# arduino_shield.net
KiCad netlist of a schematic drawn in EAGLE
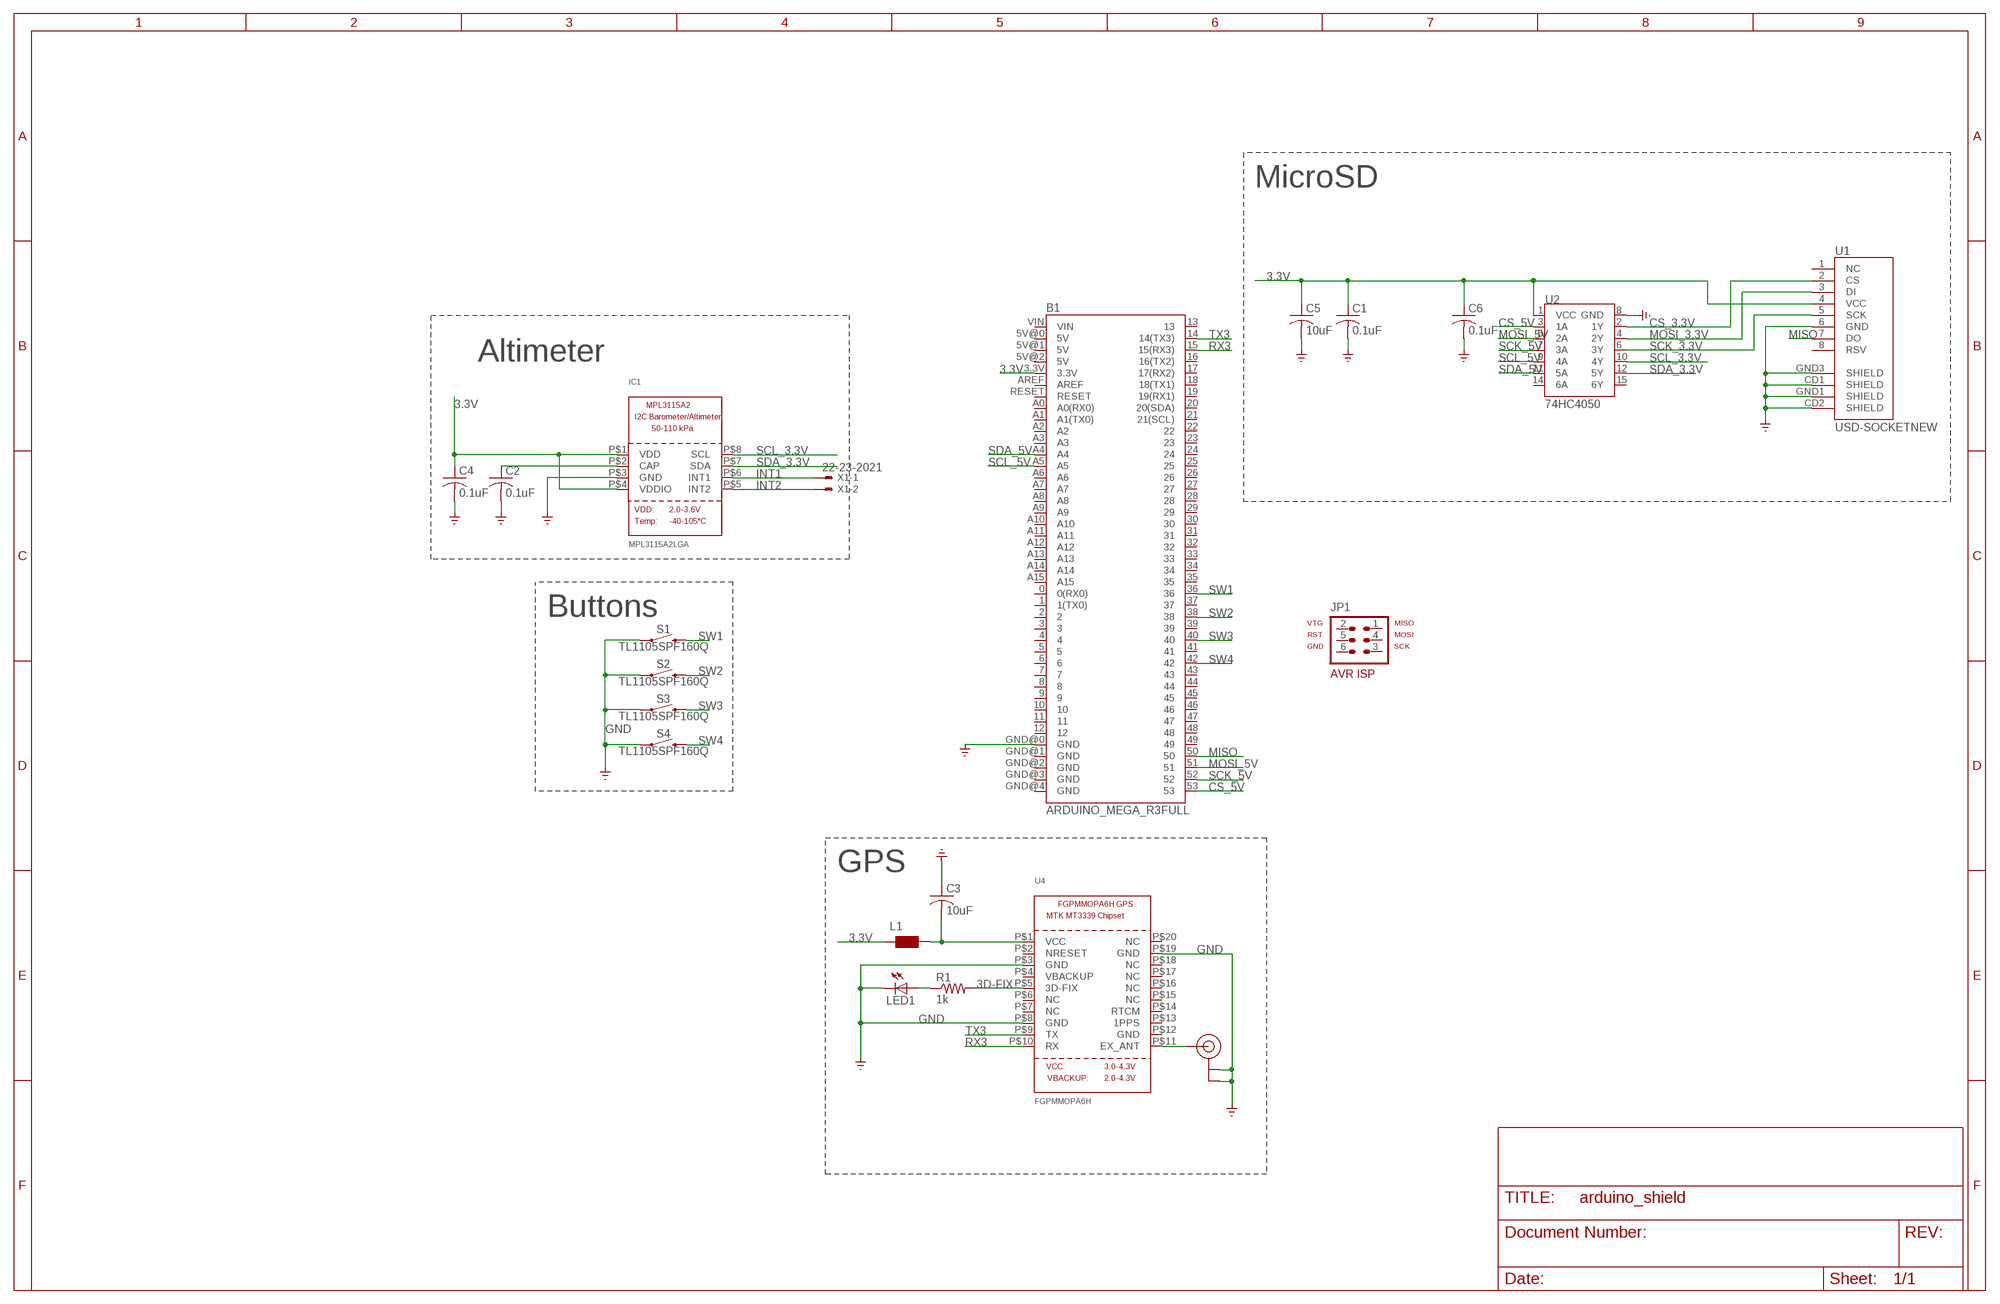
[diagram p0: schematic, sheet 1]

(export (version "E")
  (design (tool "Eeschema 10.0.6"))
  (components
    (comp (ref "B1")
      (value "ARDUINO_MEGA_R3FULL")
      (footprint "eagle-import:ARDUINO_MEGA")
      (libsource (lib "eagle-import") (part "ARDUINO_MEGA_R3FULL"))
    )
    (comp (ref "C1")
      (value "0.1uF")
      (footprint "eagle-import:C1206")
      (libsource (lib "eagle-import") (part "C-USC1206"))
    )
    (comp (ref "C2")
      (value "0.1uF")
      (footprint "eagle-import:C1206")
      (libsource (lib "eagle-import") (part "C-USC1206"))
    )
    (comp (ref "C3")
      (value "10uF")
      (footprint "eagle-import:C1206")
      (libsource (lib "eagle-import") (part "C-USC1206"))
    )
    (comp (ref "C4")
      (value "0.1uF")
      (footprint "eagle-import:C1206")
      (libsource (lib "eagle-import") (part "C-USC1206"))
    )
    (comp (ref "C5")
      (value "10uF")
      (footprint "eagle-import:C1206")
      (libsource (lib "eagle-import") (part "C-USC1206"))
    )
    (comp (ref "C6")
      (value "0.1uF")
      (footprint "eagle-import:C1206")
      (libsource (lib "eagle-import") (part "C-USC1206"))
    )
    (comp (ref "IC1")
      (value "MPL3115A2LGA")
      (footprint "eagle-import:LGA8")
      (libsource (lib "eagle-import") (part "MPL3115A2LGA"))
    )
    (comp (ref "JP1")
      (value "AVR-ISP-6")
      (footprint "eagle-import:AVR-ISP-6")
      (libsource (lib "eagle-import") (part "AVR-ISP-6"))
    )
    (comp (ref "L1")
      (value "WE-CBF_1206")
      (footprint "eagle-import:1206")
      (libsource (lib "eagle-import") (part "WE-CBF_1206"))
    )
    (comp (ref "LED1")
      (value "LEDSMT1206")
      (footprint "eagle-import:1206")
      (libsource (lib "eagle-import") (part "LEDSMT1206"))
    )
    (comp (ref "R1")
      (value "1k")
      (footprint "eagle-import:R1206")
      (libsource (lib "eagle-import") (part "R-US_R1206"))
    )
    (comp (ref "S1")
      (value "TL1105SPF160Q")
      (footprint "eagle-import:TACTILE_SWITCH_PTH_6.0MM")
      (libsource (lib "eagle-import") (part "MOMENTARY-SWITCH-SPST-PTH-6.0MM"))
    )
    (comp (ref "S2")
      (value "TL1105SPF160Q")
      (footprint "eagle-import:TACTILE_SWITCH_PTH_6.0MM")
      (libsource (lib "eagle-import") (part "MOMENTARY-SWITCH-SPST-PTH-6.0MM"))
    )
    (comp (ref "S3")
      (value "TL1105SPF160Q")
      (footprint "eagle-import:TACTILE_SWITCH_PTH_6.0MM")
      (libsource (lib "eagle-import") (part "MOMENTARY-SWITCH-SPST-PTH-6.0MM"))
    )
    (comp (ref "S4")
      (value "TL1105SPF160Q")
      (footprint "eagle-import:TACTILE_SWITCH_PTH_6.0MM")
      (libsource (lib "eagle-import") (part "MOMENTARY-SWITCH-SPST-PTH-6.0MM"))
    )
    (comp (ref "U$20")
      (value "U.FL")
      (footprint "eagle-import:U.FL")
      (libsource (lib "eagle-import") (part "U.FL"))
    )
    (comp (ref "U1")
      (value "USD-SOCKETNEW")
      (footprint "eagle-import:MICRO-SD-SOCKET-PP")
      (libsource (lib "eagle-import") (part "USD-SOCKETNEW"))
    )
    (comp (ref "U2")
      (value "74HC4050")
      (footprint "eagle-import:SO16")
      (libsource (lib "eagle-import") (part "HEX_CONVERTER"))
    )
    (comp (ref "U4")
      (value "FGPMMOPA6H")
      (footprint "eagle-import:FGPMMOPA6H")
      (libsource (lib "eagle-import") (part "GPS_FGPMMOPA6H"))
    )
    (comp (ref "X1")
      (value "22-23-2021")
      (footprint "eagle-import:22-23-2021")
      (fields (field (name "MF") "MOLEX"))
      (libsource (lib "eagle-import") (part "22-23-2021"))
    )
  )
  (nets
    (net (code "1") (name "/3.3V") (class "Default")
      (node (ref "B1") (pin "3.3V") (pinfunction "3.3V_3.3V") (pintype "bidirectional"))
      (node (ref "C1") (pin "1") (pinfunction "1_1") (pintype "passive"))
      (node (ref "C4") (pin "1") (pinfunction "1_1") (pintype "passive"))
      (node (ref "C5") (pin "1") (pinfunction "1_1") (pintype "passive"))
      (node (ref "C6") (pin "1") (pinfunction "1_1") (pintype "passive"))
      (node (ref "IC1") (pin "P$1") (pinfunction "VDD_P$1") (pintype "power_in"))
      (node (ref "IC1") (pin "P$4") (pinfunction "VDDIO_P$4") (pintype "power_in"))
      (node (ref "L1") (pin "1") (pinfunction "1_1") (pintype "passive"))
      (node (ref "U1") (pin "4") (pinfunction "VCC_4") (pintype "bidirectional"))
      (node (ref "U2") (pin "1") (pinfunction "VCC_1") (pintype "bidirectional"))
    )
    (net (code "2") (name "/3D-FIX") (class "Default")
      (node (ref "R1") (pin "2") (pinfunction "2_2") (pintype "passive"))
      (node (ref "U4") (pin "P$5") (pinfunction "3D-FIX_P$5") (pintype "bidirectional"))
    )
    (net (code "3") (name "/CS_3.3V") (class "Default")
      (node (ref "U1") (pin "2") (pinfunction "CS_2") (pintype "bidirectional"))
      (node (ref "U2") (pin "2") (pinfunction "1Y_2") (pintype "bidirectional"))
    )
    (net (code "4") (name "/CS_5V") (class "Default")
      (node (ref "B1") (pin "53") (pinfunction "53_53") (pintype "bidirectional"))
      (node (ref "U2") (pin "3") (pinfunction "1A_3") (pintype "bidirectional"))
    )
    (net (code "5") (name "/INT1") (class "Default")
      (node (ref "IC1") (pin "P$6") (pinfunction "INT1_P$6") (pintype "output"))
      (node (ref "X1") (pin "1") (pinfunction "S_1") (pintype "passive"))
    )
    (net (code "6") (name "/INT2") (class "Default")
      (node (ref "IC1") (pin "P$5") (pinfunction "INT2_P$5") (pintype "output"))
      (node (ref "X1") (pin "2") (pinfunction "S_2") (pintype "passive"))
    )
    (net (code "7") (name "/MISO") (class "Default")
      (node (ref "B1") (pin "50") (pinfunction "50_50") (pintype "bidirectional"))
      (node (ref "U1") (pin "7") (pinfunction "DO_7") (pintype "bidirectional"))
    )
    (net (code "8") (name "/MOSI_3.3V") (class "Default")
      (node (ref "U1") (pin "3") (pinfunction "DI_3") (pintype "bidirectional"))
      (node (ref "U2") (pin "4") (pinfunction "2Y_4") (pintype "bidirectional"))
    )
    (net (code "9") (name "/MOSI_5V") (class "Default")
      (node (ref "B1") (pin "51") (pinfunction "51_51") (pintype "bidirectional"))
      (node (ref "U2") (pin "5") (pinfunction "2A_5") (pintype "bidirectional"))
    )
    (net (code "10") (name "/RX3") (class "Default")
      (node (ref "B1") (pin "15") (pinfunction "15(RX3)_15") (pintype "bidirectional"))
      (node (ref "U4") (pin "P$10") (pinfunction "RX_P$10") (pintype "bidirectional"))
    )
    (net (code "11") (name "/SCK_3.3V") (class "Default")
      (node (ref "U1") (pin "5") (pinfunction "SCK_5") (pintype "bidirectional"))
      (node (ref "U2") (pin "6") (pinfunction "3Y_6") (pintype "bidirectional"))
    )
    (net (code "12") (name "/SCK_5V") (class "Default")
      (node (ref "B1") (pin "52") (pinfunction "52_52") (pintype "bidirectional"))
      (node (ref "U2") (pin "7") (pinfunction "3A_7") (pintype "bidirectional"))
    )
    (net (code "13") (name "/SCL_3.3V") (class "Default")
      (node (ref "IC1") (pin "P$8") (pinfunction "SCL_P$8") (pintype "bidirectional"))
      (node (ref "U2") (pin "10") (pinfunction "4Y_10") (pintype "bidirectional"))
    )
    (net (code "14") (name "/SCL_5V") (class "Default")
      (node (ref "B1") (pin "A5") (pinfunction "A5_A5") (pintype "bidirectional"))
      (node (ref "U2") (pin "9") (pinfunction "4A_9") (pintype "bidirectional"))
    )
    (net (code "15") (name "/SDA_3.3V") (class "Default")
      (node (ref "IC1") (pin "P$7") (pinfunction "SDA_P$7") (pintype "bidirectional"))
      (node (ref "U2") (pin "12") (pinfunction "5Y_12") (pintype "bidirectional"))
    )
    (net (code "16") (name "/SDA_5V") (class "Default")
      (node (ref "B1") (pin "A4") (pinfunction "A4_A4") (pintype "bidirectional"))
      (node (ref "U2") (pin "11") (pinfunction "5A_11") (pintype "bidirectional"))
    )
    (net (code "17") (name "/SW1") (class "Default")
      (node (ref "B1") (pin "36") (pinfunction "36_36") (pintype "bidirectional"))
      (node (ref "S1") (pin "3") (pinfunction "2_3") (pintype "passive"))
    )
    (net (code "18") (name "/SW2") (class "Default")
      (node (ref "B1") (pin "38") (pinfunction "38_38") (pintype "bidirectional"))
      (node (ref "S2") (pin "3") (pinfunction "2_3") (pintype "passive"))
    )
    (net (code "19") (name "/SW3") (class "Default")
      (node (ref "B1") (pin "40") (pinfunction "40_40") (pintype "bidirectional"))
      (node (ref "S3") (pin "3") (pinfunction "2_3") (pintype "passive"))
    )
    (net (code "20") (name "/SW4") (class "Default")
      (node (ref "B1") (pin "42") (pinfunction "42_42") (pintype "bidirectional"))
      (node (ref "S4") (pin "3") (pinfunction "2_3") (pintype "passive"))
    )
    (net (code "21") (name "/TX3") (class "Default")
      (node (ref "B1") (pin "14") (pinfunction "14(TX3)_14") (pintype "bidirectional"))
      (node (ref "U4") (pin "P$9") (pinfunction "TX_P$9") (pintype "bidirectional"))
    )
    (net (code "22") (name "GND_") (class "Default")
      (node (ref "B1") (pin "GND@0") (pinfunction "GND_GND@0") (pintype "bidirectional"))
      (node (ref "C1") (pin "2") (pinfunction "2_2") (pintype "passive"))
      (node (ref "C2") (pin "2") (pinfunction "2_2") (pintype "passive"))
      (node (ref "C3") (pin "1") (pinfunction "1_1") (pintype "passive"))
      (node (ref "C4") (pin "2") (pinfunction "2_2") (pintype "passive"))
      (node (ref "C5") (pin "2") (pinfunction "2_2") (pintype "passive"))
      (node (ref "C6") (pin "2") (pinfunction "2_2") (pintype "passive"))
      (node (ref "IC1") (pin "P$3") (pinfunction "GND_P$3") (pintype "power_in"))
      (node (ref "LED1") (pin "C") (pinfunction "C_C") (pintype "passive"))
      (node (ref "S1") (pin "1") (pinfunction "1_1") (pintype "passive"))
      (node (ref "S2") (pin "1") (pinfunction "1_1") (pintype "passive"))
      (node (ref "S3") (pin "1") (pinfunction "1_1") (pintype "passive"))
      (node (ref "S4") (pin "1") (pinfunction "1_1") (pintype "passive"))
      (node (ref "U$20") (pin "P$1") (pinfunction "GND_P$1") (pintype "bidirectional"))
      (node (ref "U$20") (pin "P$2") (pinfunction "GND_P$2") (pintype "bidirectional"))
      (node (ref "U1") (pin "6") (pinfunction "GND_6") (pintype "bidirectional"))
      (node (ref "U1") (pin "CD1") (pinfunction "SHIELD_CD1") (pintype "bidirectional"))
      (node (ref "U1") (pin "CD2") (pinfunction "SHIELD_CD2") (pintype "bidirectional"))
      (node (ref "U1") (pin "GND1") (pinfunction "SHIELD_GND1") (pintype "bidirectional"))
      (node (ref "U1") (pin "GND3") (pinfunction "SHIELD_GND3") (pintype "bidirectional"))
      (node (ref "U2") (pin "8") (pinfunction "GND_8") (pintype "bidirectional"))
      (node (ref "U4") (pin "P$19") (pinfunction "GND_P$19") (pintype "bidirectional"))
      (node (ref "U4") (pin "P$3") (pinfunction "GND_P$3") (pintype "bidirectional"))
      (node (ref "U4") (pin "P$8") (pinfunction "GND_P$8") (pintype "bidirectional"))
    )
    (net (code "23") (name "Net-(IC1-CAP)") (class "Default")
      (node (ref "C2") (pin "1") (pinfunction "1_1") (pintype "passive"))
      (node (ref "IC1") (pin "P$2") (pinfunction "CAP_P$2") (pintype "passive"))
    )
    (net (code "24") (name "Net-(LED1-PadA)") (class "Default")
      (node (ref "LED1") (pin "A") (pinfunction "A_A") (pintype "passive"))
      (node (ref "R1") (pin "1") (pinfunction "1_1") (pintype "passive"))
    )
    (net (code "25") (name "Net-(U$20-SIGNAL)") (class "Default")
      (node (ref "U$20") (pin "P$3") (pinfunction "SIGNAL_P$3") (pintype "bidirectional"))
      (node (ref "U4") (pin "P$11") (pinfunction "EX_ANT_P$11") (pintype "bidirectional"))
    )
    (net (code "26") (name "Net-(U4-VCC)") (class "Default")
      (node (ref "C3") (pin "2") (pinfunction "2_2") (pintype "passive"))
      (node (ref "L1") (pin "2") (pinfunction "2_2") (pintype "passive"))
      (node (ref "U4") (pin "P$1") (pinfunction "VCC_P$1") (pintype "bidirectional"))
    )
    (net (code "27") (name "unconnected-(B1-0(RX0)-Pad0)") (class "Default")
      (node (ref "B1") (pin "0") (pinfunction "0(RX0)_0") (pintype "bidirectional"))
    )
    (net (code "28") (name "unconnected-(B1-1(TX0)-Pad1)") (class "Default")
      (node (ref "B1") (pin "1") (pinfunction "1(TX0)_1") (pintype "bidirectional"))
    )
    (net (code "29") (name "unconnected-(B1-5V-Pad5V@0)") (class "Default")
      (node (ref "B1") (pin "5V@0") (pinfunction "5V_5V@0") (pintype "bidirectional"))
    )
    (net (code "30") (name "unconnected-(B1-5V-Pad5V@1)") (class "Default")
      (node (ref "B1") (pin "5V@1") (pinfunction "5V_5V@1") (pintype "bidirectional"))
    )
    (net (code "31") (name "unconnected-(B1-5V-Pad5V@2)") (class "Default")
      (node (ref "B1") (pin "5V@2") (pinfunction "5V_5V@2") (pintype "bidirectional"))
    )
    (net (code "32") (name "unconnected-(B1-16(TX2)-Pad16)") (class "Default")
      (node (ref "B1") (pin "16") (pinfunction "16(TX2)_16") (pintype "bidirectional"))
    )
    (net (code "33") (name "unconnected-(B1-17(RX2)-Pad17)") (class "Default")
      (node (ref "B1") (pin "17") (pinfunction "17(RX2)_17") (pintype "bidirectional"))
    )
    (net (code "34") (name "unconnected-(B1-18(TX1)-Pad18)") (class "Default")
      (node (ref "B1") (pin "18") (pinfunction "18(TX1)_18") (pintype "bidirectional"))
    )
    (net (code "35") (name "unconnected-(B1-19(RX1)-Pad19)") (class "Default")
      (node (ref "B1") (pin "19") (pinfunction "19(RX1)_19") (pintype "bidirectional"))
    )
    (net (code "36") (name "unconnected-(B1-20(SDA)-Pad20)") (class "Default")
      (node (ref "B1") (pin "20") (pinfunction "20(SDA)_20") (pintype "bidirectional"))
    )
    (net (code "37") (name "unconnected-(B1-21(SCL)-Pad21)") (class "Default")
      (node (ref "B1") (pin "21") (pinfunction "21(SCL)_21") (pintype "bidirectional"))
    )
    (net (code "38") (name "unconnected-(B1-A0(RX0)-PadA0)") (class "Default")
      (node (ref "B1") (pin "A0") (pinfunction "A0(RX0)_A0") (pintype "bidirectional"))
    )
    (net (code "39") (name "unconnected-(B1-A1(TX0)-PadA1)") (class "Default")
      (node (ref "B1") (pin "A1") (pinfunction "A1(TX0)_A1") (pintype "bidirectional"))
    )
    (net (code "40") (name "unconnected-(B1-GND-PadGND@1)") (class "Default")
      (node (ref "B1") (pin "GND@1") (pinfunction "GND_GND@1") (pintype "bidirectional"))
    )
    (net (code "41") (name "unconnected-(B1-GND-PadGND@2)") (class "Default")
      (node (ref "B1") (pin "GND@2") (pinfunction "GND_GND@2") (pintype "bidirectional"))
    )
    (net (code "42") (name "unconnected-(B1-GND-PadGND@3)") (class "Default")
      (node (ref "B1") (pin "GND@3") (pinfunction "GND_GND@3") (pintype "bidirectional"))
    )
    (net (code "43") (name "unconnected-(B1-GND-PadGND@4)") (class "Default")
      (node (ref "B1") (pin "GND@4") (pinfunction "GND_GND@4") (pintype "bidirectional"))
    )
    (net (code "44") (name "unconnected-(B1-Pad2)") (class "Default")
      (node (ref "B1") (pin "2") (pinfunction "2_2") (pintype "bidirectional"))
    )
    (net (code "45") (name "unconnected-(B1-Pad3)") (class "Default")
      (node (ref "B1") (pin "3") (pinfunction "3_3") (pintype "bidirectional"))
    )
    (net (code "46") (name "unconnected-(B1-Pad4)") (class "Default")
      (node (ref "B1") (pin "4") (pinfunction "4_4") (pintype "bidirectional"))
    )
    (net (code "47") (name "unconnected-(B1-Pad5)") (class "Default")
      (node (ref "B1") (pin "5") (pinfunction "5_5") (pintype "bidirectional"))
    )
    (net (code "48") (name "unconnected-(B1-Pad6)") (class "Default")
      (node (ref "B1") (pin "6") (pinfunction "6_6") (pintype "bidirectional"))
    )
    (net (code "49") (name "unconnected-(B1-Pad7)") (class "Default")
      (node (ref "B1") (pin "7") (pinfunction "7_7") (pintype "bidirectional"))
    )
    (net (code "50") (name "unconnected-(B1-Pad8)") (class "Default")
      (node (ref "B1") (pin "8") (pinfunction "8_8") (pintype "bidirectional"))
    )
    (net (code "51") (name "unconnected-(B1-Pad9)") (class "Default")
      (node (ref "B1") (pin "9") (pinfunction "9_9") (pintype "bidirectional"))
    )
    (net (code "52") (name "unconnected-(B1-Pad10)") (class "Default")
      (node (ref "B1") (pin "10") (pinfunction "10_10") (pintype "bidirectional"))
    )
    (net (code "53") (name "unconnected-(B1-Pad11)") (class "Default")
      (node (ref "B1") (pin "11") (pinfunction "11_11") (pintype "bidirectional"))
    )
    (net (code "54") (name "unconnected-(B1-Pad12)") (class "Default")
      (node (ref "B1") (pin "12") (pinfunction "12_12") (pintype "bidirectional"))
    )
    (net (code "55") (name "unconnected-(B1-Pad13)") (class "Default")
      (node (ref "B1") (pin "13") (pinfunction "13_13") (pintype "bidirectional"))
    )
    (net (code "56") (name "unconnected-(B1-Pad22)") (class "Default")
      (node (ref "B1") (pin "22") (pinfunction "22_22") (pintype "bidirectional"))
    )
    (net (code "57") (name "unconnected-(B1-Pad23)") (class "Default")
      (node (ref "B1") (pin "23") (pinfunction "23_23") (pintype "bidirectional"))
    )
    (net (code "58") (name "unconnected-(B1-Pad24)") (class "Default")
      (node (ref "B1") (pin "24") (pinfunction "24_24") (pintype "bidirectional"))
    )
    (net (code "59") (name "unconnected-(B1-Pad25)") (class "Default")
      (node (ref "B1") (pin "25") (pinfunction "25_25") (pintype "bidirectional"))
    )
    (net (code "60") (name "unconnected-(B1-Pad26)") (class "Default")
      (node (ref "B1") (pin "26") (pinfunction "26_26") (pintype "bidirectional"))
    )
    (net (code "61") (name "unconnected-(B1-Pad27)") (class "Default")
      (node (ref "B1") (pin "27") (pinfunction "27_27") (pintype "bidirectional"))
    )
    (net (code "62") (name "unconnected-(B1-Pad28)") (class "Default")
      (node (ref "B1") (pin "28") (pinfunction "28_28") (pintype "bidirectional"))
    )
    (net (code "63") (name "unconnected-(B1-Pad29)") (class "Default")
      (node (ref "B1") (pin "29") (pinfunction "29_29") (pintype "bidirectional"))
    )
    (net (code "64") (name "unconnected-(B1-Pad30)") (class "Default")
      (node (ref "B1") (pin "30") (pinfunction "30_30") (pintype "bidirectional"))
    )
    (net (code "65") (name "unconnected-(B1-Pad31)") (class "Default")
      (node (ref "B1") (pin "31") (pinfunction "31_31") (pintype "bidirectional"))
    )
    (net (code "66") (name "unconnected-(B1-Pad32)") (class "Default")
      (node (ref "B1") (pin "32") (pinfunction "32_32") (pintype "bidirectional"))
    )
    (net (code "67") (name "unconnected-(B1-Pad33)") (class "Default")
      (node (ref "B1") (pin "33") (pinfunction "33_33") (pintype "bidirectional"))
    )
    (net (code "68") (name "unconnected-(B1-Pad34)") (class "Default")
      (node (ref "B1") (pin "34") (pinfunction "34_34") (pintype "bidirectional"))
    )
    (net (code "69") (name "unconnected-(B1-Pad35)") (class "Default")
      (node (ref "B1") (pin "35") (pinfunction "35_35") (pintype "bidirectional"))
    )
    (net (code "70") (name "unconnected-(B1-Pad37)") (class "Default")
      (node (ref "B1") (pin "37") (pinfunction "37_37") (pintype "bidirectional"))
    )
    (net (code "71") (name "unconnected-(B1-Pad39)") (class "Default")
      (node (ref "B1") (pin "39") (pinfunction "39_39") (pintype "bidirectional"))
    )
    (net (code "72") (name "unconnected-(B1-Pad41)") (class "Default")
      (node (ref "B1") (pin "41") (pinfunction "41_41") (pintype "bidirectional"))
    )
    (net (code "73") (name "unconnected-(B1-Pad43)") (class "Default")
      (node (ref "B1") (pin "43") (pinfunction "43_43") (pintype "bidirectional"))
    )
    (net (code "74") (name "unconnected-(B1-Pad44)") (class "Default")
      (node (ref "B1") (pin "44") (pinfunction "44_44") (pintype "bidirectional"))
    )
    (net (code "75") (name "unconnected-(B1-Pad45)") (class "Default")
      (node (ref "B1") (pin "45") (pinfunction "45_45") (pintype "bidirectional"))
    )
    (net (code "76") (name "unconnected-(B1-Pad46)") (class "Default")
      (node (ref "B1") (pin "46") (pinfunction "46_46") (pintype "bidirectional"))
    )
    (net (code "77") (name "unconnected-(B1-Pad47)") (class "Default")
      (node (ref "B1") (pin "47") (pinfunction "47_47") (pintype "bidirectional"))
    )
    (net (code "78") (name "unconnected-(B1-Pad48)") (class "Default")
      (node (ref "B1") (pin "48") (pinfunction "48_48") (pintype "bidirectional"))
    )
    (net (code "79") (name "unconnected-(B1-Pad49)") (class "Default")
      (node (ref "B1") (pin "49") (pinfunction "49_49") (pintype "bidirectional"))
    )
    (net (code "80") (name "unconnected-(B1-PadA2)") (class "Default")
      (node (ref "B1") (pin "A2") (pinfunction "A2_A2") (pintype "bidirectional"))
    )
    (net (code "81") (name "unconnected-(B1-PadA3)") (class "Default")
      (node (ref "B1") (pin "A3") (pinfunction "A3_A3") (pintype "bidirectional"))
    )
    (net (code "82") (name "unconnected-(B1-PadA6)") (class "Default")
      (node (ref "B1") (pin "A6") (pinfunction "A6_A6") (pintype "bidirectional"))
    )
    (net (code "83") (name "unconnected-(B1-PadA7)") (class "Default")
      (node (ref "B1") (pin "A7") (pinfunction "A7_A7") (pintype "bidirectional"))
    )
    (net (code "84") (name "unconnected-(B1-PadA8)") (class "Default")
      (node (ref "B1") (pin "A8") (pinfunction "A8_A8") (pintype "bidirectional"))
    )
    (net (code "85") (name "unconnected-(B1-PadA9)") (class "Default")
      (node (ref "B1") (pin "A9") (pinfunction "A9_A9") (pintype "bidirectional"))
    )
    (net (code "86") (name "unconnected-(B1-PadA10)") (class "Default")
      (node (ref "B1") (pin "A10") (pinfunction "A10_A10") (pintype "bidirectional"))
    )
    (net (code "87") (name "unconnected-(B1-PadA11)") (class "Default")
      (node (ref "B1") (pin "A11") (pinfunction "A11_A11") (pintype "bidirectional"))
    )
    (net (code "88") (name "unconnected-(B1-PadA12)") (class "Default")
      (node (ref "B1") (pin "A12") (pinfunction "A12_A12") (pintype "bidirectional"))
    )
    (net (code "89") (name "unconnected-(B1-PadA13)") (class "Default")
      (node (ref "B1") (pin "A13") (pinfunction "A13_A13") (pintype "bidirectional"))
    )
    (net (code "90") (name "unconnected-(B1-PadA14)") (class "Default")
      (node (ref "B1") (pin "A14") (pinfunction "A14_A14") (pintype "bidirectional"))
    )
    (net (code "91") (name "unconnected-(B1-PadA15)") (class "Default")
      (node (ref "B1") (pin "A15") (pinfunction "A15_A15") (pintype "bidirectional"))
    )
    (net (code "92") (name "unconnected-(B1-PadAREF)") (class "Default")
      (node (ref "B1") (pin "AREF") (pinfunction "AREF_AREF") (pintype "bidirectional"))
    )
    (net (code "93") (name "unconnected-(B1-PadRESET)") (class "Default")
      (node (ref "B1") (pin "RESET") (pinfunction "RESET_RESET") (pintype "bidirectional"))
    )
    (net (code "94") (name "unconnected-(B1-PadVIN)") (class "Default")
      (node (ref "B1") (pin "VIN") (pinfunction "VIN_VIN") (pintype "bidirectional"))
    )
    (net (code "95") (name "unconnected-(JP1-Pad1)") (class "Default")
      (node (ref "JP1") (pin "1") (pinfunction "1_1") (pintype "passive"))
    )
    (net (code "96") (name "unconnected-(JP1-Pad2)") (class "Default")
      (node (ref "JP1") (pin "2") (pinfunction "2_2") (pintype "passive"))
    )
    (net (code "97") (name "unconnected-(JP1-Pad3)") (class "Default")
      (node (ref "JP1") (pin "3") (pinfunction "3_3") (pintype "passive"))
    )
    (net (code "98") (name "unconnected-(JP1-Pad4)") (class "Default")
      (node (ref "JP1") (pin "4") (pinfunction "4_4") (pintype "passive"))
    )
    (net (code "99") (name "unconnected-(JP1-Pad5)") (class "Default")
      (node (ref "JP1") (pin "5") (pinfunction "5_5") (pintype "passive"))
    )
    (net (code "100") (name "unconnected-(JP1-Pad6)") (class "Default")
      (node (ref "JP1") (pin "6") (pinfunction "6_6") (pintype "passive"))
    )
    (net (code "101") (name "unconnected-(U1-NC-Pad1)") (class "Default")
      (node (ref "U1") (pin "1") (pinfunction "NC_1") (pintype "bidirectional"))
    )
    (net (code "102") (name "unconnected-(U1-RSV-Pad8)") (class "Default")
      (node (ref "U1") (pin "8") (pinfunction "RSV_8") (pintype "bidirectional"))
    )
    (net (code "103") (name "unconnected-(U2-6A-Pad14)") (class "Default")
      (node (ref "U2") (pin "14") (pinfunction "6A_14") (pintype "bidirectional"))
    )
    (net (code "104") (name "unconnected-(U2-6Y-Pad15)") (class "Default")
      (node (ref "U2") (pin "15") (pinfunction "6Y_15") (pintype "bidirectional"))
    )
    (net (code "105") (name "unconnected-(U4-1PPS-PadP$13)") (class "Default")
      (node (ref "U4") (pin "P$13") (pinfunction "1PPS_P$13") (pintype "bidirectional"))
    )
    (net (code "106") (name "unconnected-(U4-GND-PadP$12)") (class "Default")
      (node (ref "U4") (pin "P$12") (pinfunction "GND_P$12") (pintype "bidirectional"))
    )
    (net (code "107") (name "unconnected-(U4-NC-PadP$6)") (class "Default")
      (node (ref "U4") (pin "P$6") (pinfunction "NC_P$6") (pintype "bidirectional"))
    )
    (net (code "108") (name "unconnected-(U4-NC-PadP$7)") (class "Default")
      (node (ref "U4") (pin "P$7") (pinfunction "NC_P$7") (pintype "bidirectional"))
    )
    (net (code "109") (name "unconnected-(U4-NC-PadP$15)") (class "Default")
      (node (ref "U4") (pin "P$15") (pinfunction "NC_P$15") (pintype "bidirectional"))
    )
    (net (code "110") (name "unconnected-(U4-NC-PadP$16)") (class "Default")
      (node (ref "U4") (pin "P$16") (pinfunction "NC_P$16") (pintype "bidirectional"))
    )
    (net (code "111") (name "unconnected-(U4-NC-PadP$17)") (class "Default")
      (node (ref "U4") (pin "P$17") (pinfunction "NC_P$17") (pintype "bidirectional"))
    )
    (net (code "112") (name "unconnected-(U4-NC-PadP$18)") (class "Default")
      (node (ref "U4") (pin "P$18") (pinfunction "NC_P$18") (pintype "bidirectional"))
    )
    (net (code "113") (name "unconnected-(U4-NC-PadP$20)") (class "Default")
      (node (ref "U4") (pin "P$20") (pinfunction "NC_P$20") (pintype "bidirectional"))
    )
    (net (code "114") (name "unconnected-(U4-NRESET-PadP$2)") (class "Default")
      (node (ref "U4") (pin "P$2") (pinfunction "NRESET_P$2") (pintype "bidirectional"))
    )
    (net (code "115") (name "unconnected-(U4-RTCM-PadP$14)") (class "Default")
      (node (ref "U4") (pin "P$14") (pinfunction "RTCM_P$14") (pintype "bidirectional"))
    )
    (net (code "116") (name "unconnected-(U4-VBACKUP-PadP$4)") (class "Default")
      (node (ref "U4") (pin "P$4") (pinfunction "VBACKUP_P$4") (pintype "bidirectional"))
    )
  )
)
